# picoAvaR8.net
KiCad netlist of a schematic drawn in EAGLE
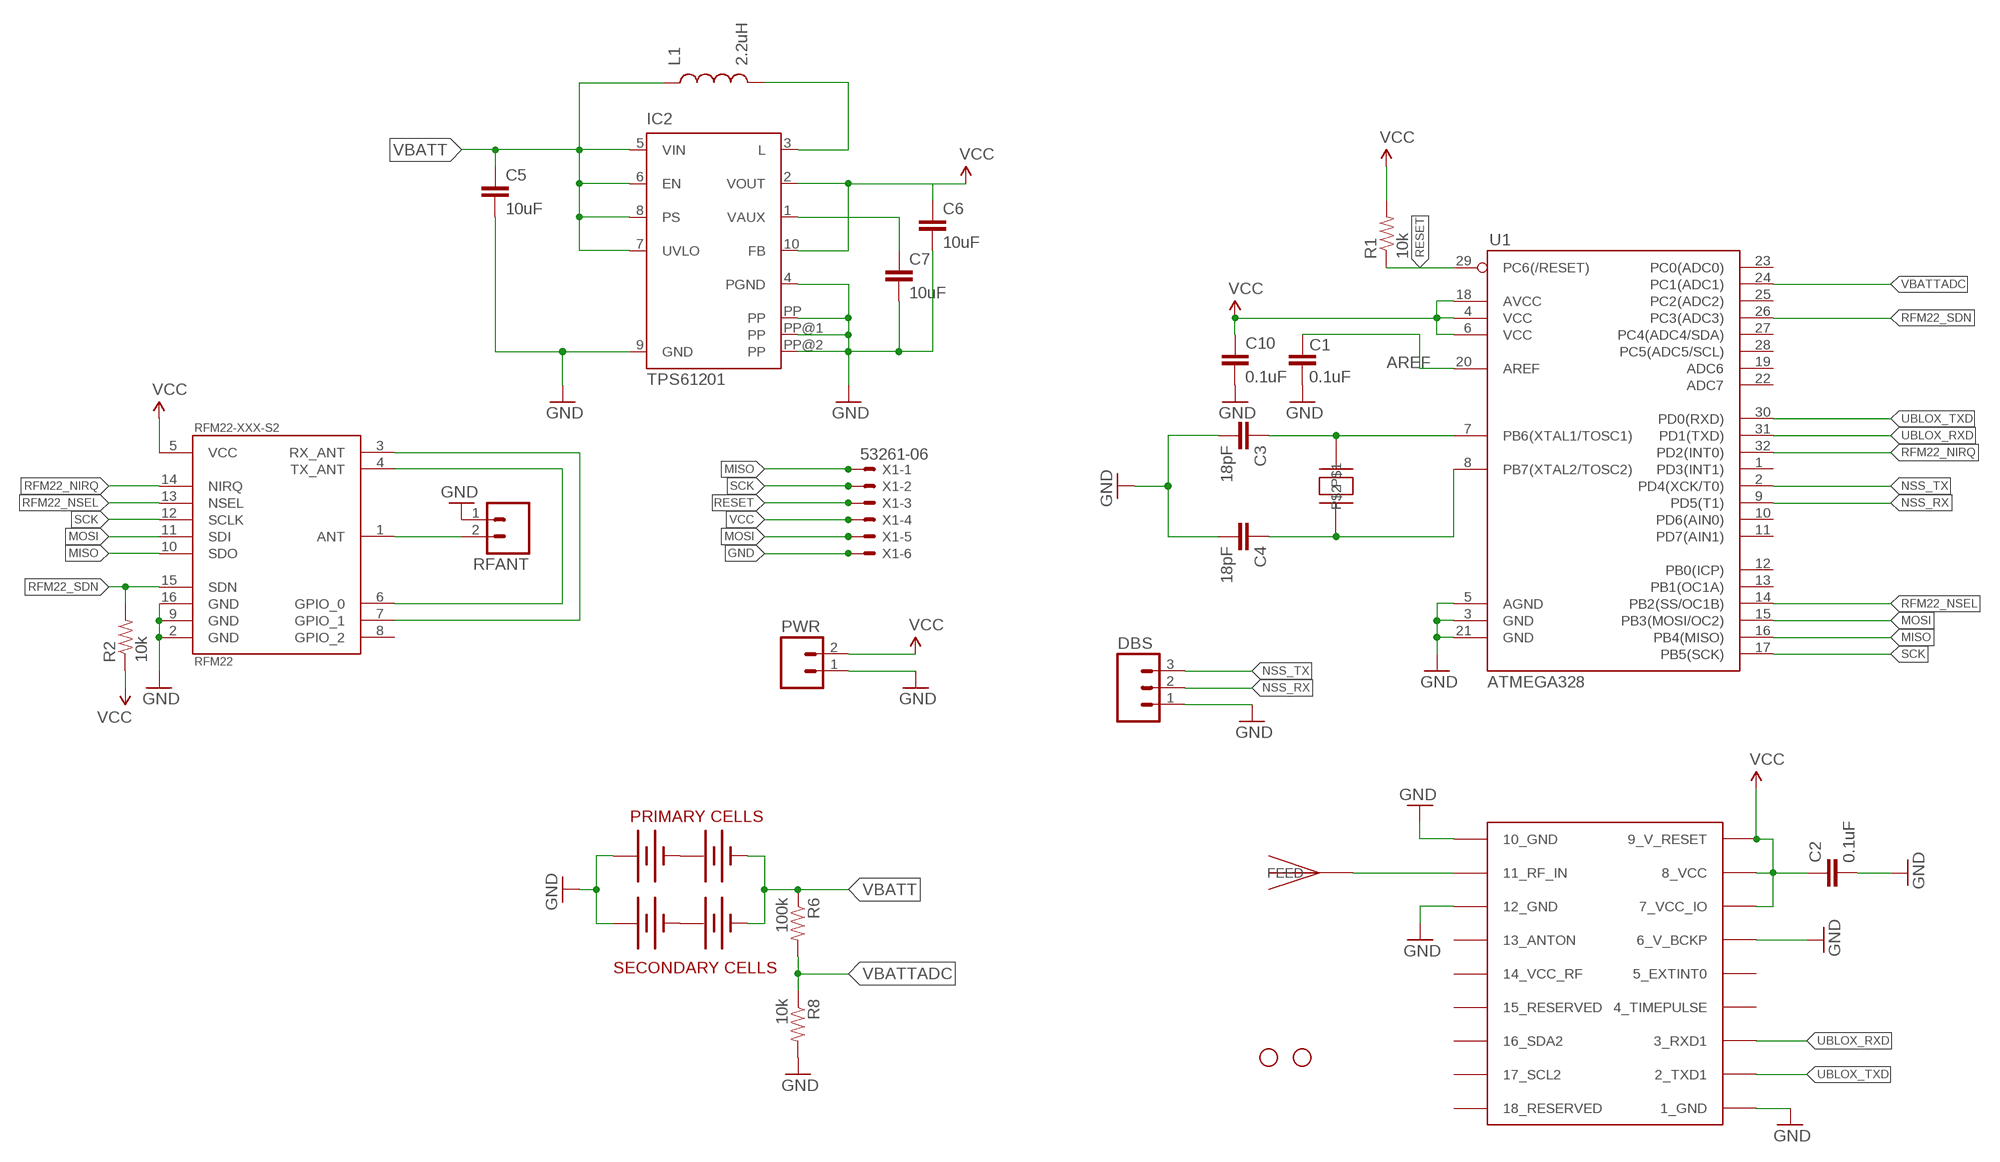
[diagram p0: schematic, sheet 1]

(export (version "E")
  (design (tool "Eeschema 10.0.6"))
  (components
    (comp (ref "C1")
      (value "0.1uF")
      (footprint "eagle-import:0402-CAP")
      (libsource (lib "eagle-import") (part "CAP0402-CAP"))
    )
    (comp (ref "C2")
      (value "0.1uF")
      (footprint "eagle-import:0402-CAP")
      (libsource (lib "eagle-import") (part "CAP0402-CAP"))
    )
    (comp (ref "C3")
      (value "18pF")
      (footprint "eagle-import:0402-CAP")
      (libsource (lib "eagle-import") (part "CAP0402-CAP"))
    )
    (comp (ref "C4")
      (value "18pF")
      (footprint "eagle-import:0402-CAP")
      (libsource (lib "eagle-import") (part "CAP0402-CAP"))
    )
    (comp (ref "C5")
      (value "10uF")
      (footprint "eagle-import:1206")
      (libsource (lib "eagle-import") (part "CAP1206"))
    )
    (comp (ref "C6")
      (value "10uF")
      (footprint "eagle-import:1206")
      (libsource (lib "eagle-import") (part "CAP1206"))
    )
    (comp (ref "C7")
      (value "10uF")
      (footprint "eagle-import:1206")
      (libsource (lib "eagle-import") (part "CAP1206"))
    )
    (comp (ref "C10")
      (value "0.1uF")
      (footprint "eagle-import:0402-CAP")
      (libsource (lib "eagle-import") (part "CAP0402-CAP"))
    )
    (comp (ref "DBS")
      (value "M03PTH")
      (footprint "eagle-import:1X03")
      (libsource (lib "eagle-import") (part "M03PTH"))
    )
    (comp (ref "IC2")
      (value "TPS61201")
      (footprint "eagle-import:S-PDSO-N10")
      (fields (field (name "MPN") "TPS61201DRCT"))
      (libsource (lib "eagle-import") (part "TPS61201"))
    )
    (comp (ref "JP1")
      (value "STAND-OFF")
      (footprint "eagle-import:STAND-OFF")
      (libsource (lib "eagle-import") (part "STAND-OFF"))
    )
    (comp (ref "JP2")
      (value "STAND-OFF")
      (footprint "eagle-import:STAND-OFF")
      (libsource (lib "eagle-import") (part "STAND-OFF"))
    )
    (comp (ref "L1")
      (value "2.2uH")
      (footprint "eagle-import:ELLVGG_INDUCTOR")
      (libsource (lib "eagle-import") (part "ELLVGG_INDUCTOR"))
    )
    (comp (ref "PC1")
      (value "PC1")
      (footprint "eagle-import:TEST")
      (libsource (lib "eagle-import") (part "TEST"))
    )
    (comp (ref "PC2")
      (value "TEST")
      (footprint "eagle-import:TEST")
      (libsource (lib "eagle-import") (part "TEST"))
    )
    (comp (ref "PWR")
      (value "M02PTH")
      (footprint "eagle-import:1X02")
      (libsource (lib "eagle-import") (part "M02PTH"))
    )
    (comp (ref "R1")
      (value "10k")
      (footprint "eagle-import:0402-RES")
      (libsource (lib "eagle-import") (part "RESISTOR0402-RES"))
    )
    (comp (ref "R2")
      (value "10k")
      (footprint "eagle-import:0402-RES")
      (libsource (lib "eagle-import") (part "RESISTOR0402-RES"))
    )
    (comp (ref "R6")
      (value "100k")
      (footprint "eagle-import:0402-RES")
      (libsource (lib "eagle-import") (part "RESISTOR0402-RES"))
    )
    (comp (ref "R8")
      (value "10k")
      (footprint "eagle-import:0402-RES")
      (libsource (lib "eagle-import") (part "RESISTOR0402-RES"))
    )
    (comp (ref "RFANT")
      (value "M02PTH")
      (footprint "eagle-import:1X02")
      (libsource (lib "eagle-import") (part "M02PTH"))
    )
    (comp (ref "RFM22-XXX-S2")
      (value "RFM22")
      (footprint "eagle-import:RFM22-XXX-S2")
      (libsource (lib "eagle-import") (part "RFM22"))
    )
    (comp (ref "SC1")
      (value "TEST")
      (footprint "eagle-import:TEST")
      (libsource (lib "eagle-import") (part "TEST"))
    )
    (comp (ref "SC2")
      (value "TEST")
      (footprint "eagle-import:TEST")
      (libsource (lib "eagle-import") (part "TEST"))
    )
    (comp (ref "U$1")
      (value "UBLOX_MAX-6")
      (footprint "eagle-import:UBLOX_MAX-6")
      (libsource (lib "eagle-import") (part "UBLOX_MAX-6"))
    )
    (comp (ref "U$2")
      (value "ABRACON_ABM3_CRYSTAL")
      (footprint "eagle-import:ABRACON_ABM3_CRYSTAL")
      (libsource (lib "eagle-import") (part "ABRACON_ABM3_CRYSTAL"))
    )
    (comp (ref "U$3")
      (value "JTI_ANTENNA-1575AT43A40")
      (footprint "eagle-import:JTI_ANTENNA-1575AT43A40")
      (libsource (lib "eagle-import") (part "JTI_ANTENNA-1575AT43A40"))
    )
    (comp (ref "U1")
      (value "ATMEGA328")
      (footprint "eagle-import:TQFP32-08")
      (libsource (lib "eagle-import") (part "ATMEGA168"))
    )
    (comp (ref "X1")
      (value "53261-06")
      (footprint "eagle-import:53261-06")
      (libsource (lib "eagle-import") (part "53?-06261"))
    )
  )
  (nets
    (net (code "1") (name "/AREF") (class "Default")
      (node (ref "C1") (pin "2") (pinfunction "2_2") (pintype "passive"))
      (node (ref "U1") (pin "20") (pinfunction "AREF_20") (pintype "bidirectional"))
    )
    (net (code "2") (name "GND") (class "Default")
      (node (ref "C1") (pin "1") (pinfunction "1_1") (pintype "passive"))
      (node (ref "C10") (pin "2") (pinfunction "2_2") (pintype "passive"))
      (node (ref "C2") (pin "2") (pinfunction "2_2") (pintype "passive"))
      (node (ref "C3") (pin "2") (pinfunction "2_2") (pintype "passive"))
      (node (ref "C4") (pin "2") (pinfunction "2_2") (pintype "passive"))
      (node (ref "C5") (pin "2") (pinfunction "2_2") (pintype "passive"))
      (node (ref "C6") (pin "2") (pinfunction "2_2") (pintype "passive"))
      (node (ref "C7") (pin "2") (pinfunction "2_2") (pintype "passive"))
      (node (ref "DBS") (pin "1") (pinfunction "1_1") (pintype "passive"))
      (node (ref "IC2") (pin "4") (pinfunction "PGND_4") (pintype "power_in"))
      (node (ref "IC2") (pin "9") (pinfunction "GND_9") (pintype "power_in"))
      (node (ref "IC2") (pin "PP") (pinfunction "PP_PP") (pintype "power_in"))
      (node (ref "IC2") (pin "PP@1") (pinfunction "PP_PP@1") (pintype "power_in"))
      (node (ref "IC2") (pin "PP@2") (pinfunction "PP_PP@2") (pintype "power_in"))
      (node (ref "PC1") (pin "VBATT") (pinfunction "+_VBATT") (pintype "power_in"))
      (node (ref "PC1") (pin "VBATT1") (pinfunction "+_VBATT1") (pintype "power_in"))
      (node (ref "PWR") (pin "1") (pinfunction "1_1") (pintype "passive"))
      (node (ref "R8") (pin "2") (pinfunction "2_2") (pintype "passive"))
      (node (ref "RFANT") (pin "1") (pinfunction "1_1") (pintype "passive"))
      (node (ref "RFM22-XXX-S2") (pin "16") (pinfunction "GND_16") (pintype "power_in"))
      (node (ref "RFM22-XXX-S2") (pin "2") (pinfunction "GND_2") (pintype "power_in"))
      (node (ref "RFM22-XXX-S2") (pin "9") (pinfunction "GND_9") (pintype "power_in"))
      (node (ref "SC1") (pin "VBATT") (pinfunction "+_VBATT") (pintype "power_in"))
      (node (ref "SC1") (pin "VBATT1") (pinfunction "+_VBATT1") (pintype "power_in"))
      (node (ref "U$1") (pin "10_GND") (pinfunction "10_GND_10_GND") (pintype "bidirectional"))
      (node (ref "U$1") (pin "12_GND") (pinfunction "12_GND_12_GND") (pintype "bidirectional"))
      (node (ref "U$1") (pin "1_GND") (pinfunction "1_GND_1_GND") (pintype "bidirectional"))
      (node (ref "U$1") (pin "6_V_BCKP") (pinfunction "6_V_BCKP_6_V_BCKP") (pintype "bidirectional"))
      (node (ref "U1") (pin "21") (pinfunction "GND_21") (pintype "bidirectional"))
      (node (ref "U1") (pin "3") (pinfunction "GND_3") (pintype "bidirectional"))
      (node (ref "U1") (pin "5") (pinfunction "AGND_5") (pintype "bidirectional"))
      (node (ref "X1") (pin "6") (pinfunction "S_6") (pintype "passive"))
    )
    (net (code "3") (name "MISO") (class "Default")
      (node (ref "RFM22-XXX-S2") (pin "10") (pinfunction "SDO_10") (pintype "output"))
      (node (ref "U1") (pin "16") (pinfunction "PB4(MISO)_16") (pintype "bidirectional"))
      (node (ref "X1") (pin "1") (pinfunction "S_1") (pintype "passive"))
    )
    (net (code "4") (name "MOSI") (class "Default")
      (node (ref "RFM22-XXX-S2") (pin "11") (pinfunction "SDI_11") (pintype "input"))
      (node (ref "U1") (pin "15") (pinfunction "PB3(MOSI/OC2)_15") (pintype "bidirectional"))
      (node (ref "X1") (pin "5") (pinfunction "S_5") (pintype "passive"))
    )
    (net (code "5") (name "NSS_RX") (class "Default")
      (node (ref "DBS") (pin "2") (pinfunction "2_2") (pintype "passive"))
      (node (ref "U1") (pin "9") (pinfunction "PD5(T1)_9") (pintype "bidirectional"))
    )
    (net (code "6") (name "NSS_TX") (class "Default")
      (node (ref "DBS") (pin "3") (pinfunction "3_3") (pintype "passive"))
      (node (ref "U1") (pin "2") (pinfunction "PD4(XCK/T0)_2") (pintype "bidirectional"))
    )
    (net (code "7") (name "Net-(IC2-L)") (class "Default")
      (node (ref "IC2") (pin "3") (pinfunction "L_3") (pintype "input"))
      (node (ref "L1") (pin "P$2") (pinfunction "2_P$2") (pintype "passive"))
    )
    (net (code "8") (name "Net-(IC2-VAUX)") (class "Default")
      (node (ref "C7") (pin "1") (pinfunction "1_1") (pintype "passive"))
      (node (ref "IC2") (pin "1") (pinfunction "VAUX_1") (pintype "bidirectional"))
    )
    (net (code "9") (name "Net-(PC1---PadGND)") (class "Default")
      (node (ref "PC1") (pin "GND") (pinfunction "-_GND") (pintype "power_in"))
      (node (ref "PC1") (pin "GND2") (pinfunction "-_GND2") (pintype "power_in"))
      (node (ref "PC2") (pin "VBATT") (pinfunction "+_VBATT") (pintype "power_in"))
      (node (ref "PC2") (pin "VBATT1") (pinfunction "+_VBATT1") (pintype "power_in"))
    )
    (net (code "10") (name "Net-(RFM22-XXX-S2-ANT)") (class "Default")
      (node (ref "RFANT") (pin "2") (pinfunction "2_2") (pintype "passive"))
      (node (ref "RFM22-XXX-S2") (pin "1") (pinfunction "ANT_1") (pintype "bidirectional"))
    )
    (net (code "11") (name "Net-(RFM22-XXX-S2-GPIO_0)") (class "Default")
      (node (ref "RFM22-XXX-S2") (pin "4") (pinfunction "TX_ANT_4") (pintype "input"))
      (node (ref "RFM22-XXX-S2") (pin "6") (pinfunction "GPIO_0_6") (pintype "bidirectional"))
    )
    (net (code "12") (name "Net-(RFM22-XXX-S2-GPIO_1)") (class "Default")
      (node (ref "RFM22-XXX-S2") (pin "3") (pinfunction "RX_ANT_3") (pintype "input"))
      (node (ref "RFM22-XXX-S2") (pin "7") (pinfunction "GPIO_1_7") (pintype "bidirectional"))
    )
    (net (code "13") (name "Net-(SC1---PadGND)") (class "Default")
      (node (ref "SC1") (pin "GND") (pinfunction "-_GND") (pintype "power_in"))
      (node (ref "SC1") (pin "GND2") (pinfunction "-_GND2") (pintype "power_in"))
      (node (ref "SC2") (pin "VBATT") (pinfunction "+_VBATT") (pintype "power_in"))
      (node (ref "SC2") (pin "VBATT1") (pinfunction "+_VBATT1") (pintype "power_in"))
    )
    (net (code "14") (name "Net-(U$1-Pad11_RF_IN)") (class "Default")
      (node (ref "U$1") (pin "11_RF_IN") (pinfunction "11_RF_IN_11_RF_IN") (pintype "bidirectional"))
      (node (ref "U$3") (pin "FEED") (pinfunction "FEED_FEED") (pintype "bidirectional"))
    )
    (net (code "15") (name "Net-(U1-PB6(XTAL1{slash}TOSC1))") (class "Default")
      (node (ref "C3") (pin "1") (pinfunction "1_1") (pintype "passive"))
      (node (ref "U$2") (pin "P$2") (pinfunction "P$2_P$2") (pintype "bidirectional"))
      (node (ref "U1") (pin "7") (pinfunction "PB6(XTAL1/TOSC1)_7") (pintype "bidirectional"))
    )
    (net (code "16") (name "Net-(U1-PB7(XTAL2{slash}TOSC2))") (class "Default")
      (node (ref "C4") (pin "1") (pinfunction "1_1") (pintype "passive"))
      (node (ref "U$2") (pin "P$1") (pinfunction "P$1_P$1") (pintype "bidirectional"))
      (node (ref "U1") (pin "8") (pinfunction "PB7(XTAL2/TOSC2)_8") (pintype "bidirectional"))
    )
    (net (code "17") (name "RESET") (class "Default")
      (node (ref "R1") (pin "1") (pinfunction "1_1") (pintype "passive"))
      (node (ref "U1") (pin "29") (pinfunction "PC6(/RESET)_29") (pintype "bidirectional"))
      (node (ref "X1") (pin "3") (pinfunction "S_3") (pintype "passive"))
    )
    (net (code "18") (name "RFM22_NIRQ") (class "Default")
      (node (ref "RFM22-XXX-S2") (pin "14") (pinfunction "NIRQ_14") (pintype "output"))
      (node (ref "U1") (pin "32") (pinfunction "PD2(INT0)_32") (pintype "bidirectional"))
    )
    (net (code "19") (name "RFM22_NSEL") (class "Default")
      (node (ref "RFM22-XXX-S2") (pin "13") (pinfunction "NSEL_13") (pintype "input"))
      (node (ref "U1") (pin "14") (pinfunction "PB2(SS/OC1B)_14") (pintype "bidirectional"))
    )
    (net (code "20") (name "RFM22_SDN") (class "Default")
      (node (ref "R2") (pin "2") (pinfunction "2_2") (pintype "passive"))
      (node (ref "RFM22-XXX-S2") (pin "15") (pinfunction "SDN_15") (pintype "input"))
      (node (ref "U1") (pin "26") (pinfunction "PC3(ADC3)_26") (pintype "bidirectional"))
    )
    (net (code "21") (name "SCK") (class "Default")
      (node (ref "RFM22-XXX-S2") (pin "12") (pinfunction "SCLK_12") (pintype "input"))
      (node (ref "U1") (pin "17") (pinfunction "PB5(SCK)_17") (pintype "bidirectional"))
      (node (ref "X1") (pin "2") (pinfunction "S_2") (pintype "passive"))
    )
    (net (code "22") (name "UBLOX_RXD") (class "Default")
      (node (ref "U$1") (pin "3_RXD1") (pinfunction "3_RXD1_3_RXD1") (pintype "bidirectional"))
      (node (ref "U1") (pin "31") (pinfunction "PD1(TXD)_31") (pintype "bidirectional"))
    )
    (net (code "23") (name "UBLOX_TXD") (class "Default")
      (node (ref "U$1") (pin "2_TXD1") (pinfunction "2_TXD1_2_TXD1") (pintype "bidirectional"))
      (node (ref "U1") (pin "30") (pinfunction "PD0(RXD)_30") (pintype "bidirectional"))
    )
    (net (code "24") (name "VBATT") (class "Default")
      (node (ref "C5") (pin "1") (pinfunction "1_1") (pintype "passive"))
      (node (ref "IC2") (pin "5") (pinfunction "VIN_5") (pintype "input"))
      (node (ref "IC2") (pin "6") (pinfunction "EN_6") (pintype "input"))
      (node (ref "IC2") (pin "7") (pinfunction "UVLO_7") (pintype "input"))
      (node (ref "IC2") (pin "8") (pinfunction "PS_8") (pintype "input"))
      (node (ref "L1") (pin "P$1") (pinfunction "1_P$1") (pintype "passive"))
      (node (ref "PC2") (pin "GND") (pinfunction "-_GND") (pintype "power_in"))
      (node (ref "PC2") (pin "GND2") (pinfunction "-_GND2") (pintype "power_in"))
      (node (ref "R6") (pin "1") (pinfunction "1_1") (pintype "passive"))
      (node (ref "SC2") (pin "GND") (pinfunction "-_GND") (pintype "power_in"))
      (node (ref "SC2") (pin "GND2") (pinfunction "-_GND2") (pintype "power_in"))
    )
    (net (code "25") (name "VBATTADC") (class "Default")
      (node (ref "R6") (pin "2") (pinfunction "2_2") (pintype "passive"))
      (node (ref "R8") (pin "1") (pinfunction "1_1") (pintype "passive"))
      (node (ref "U1") (pin "24") (pinfunction "PC1(ADC1)_24") (pintype "bidirectional"))
    )
    (net (code "26") (name "VCC") (class "Default")
      (node (ref "C10") (pin "1") (pinfunction "1_1") (pintype "passive"))
      (node (ref "C2") (pin "1") (pinfunction "1_1") (pintype "passive"))
      (node (ref "C6") (pin "1") (pinfunction "1_1") (pintype "passive"))
      (node (ref "IC2") (pin "10") (pinfunction "FB_10") (pintype "input"))
      (node (ref "IC2") (pin "2") (pinfunction "VOUT_2") (pintype "passive"))
      (node (ref "PWR") (pin "2") (pinfunction "2_2") (pintype "passive"))
      (node (ref "R1") (pin "2") (pinfunction "2_2") (pintype "passive"))
      (node (ref "R2") (pin "1") (pinfunction "1_1") (pintype "passive"))
      (node (ref "RFM22-XXX-S2") (pin "5") (pinfunction "VCC_5") (pintype "bidirectional"))
      (node (ref "U$1") (pin "7_VCC_IO") (pinfunction "7_VCC_IO_7_VCC_IO") (pintype "bidirectional"))
      (node (ref "U$1") (pin "8_VCC") (pinfunction "8_VCC_8_VCC") (pintype "bidirectional"))
      (node (ref "U$1") (pin "9_V_RESET") (pinfunction "9_V_RESET_9_V_RESET") (pintype "bidirectional"))
      (node (ref "U1") (pin "18") (pinfunction "AVCC_18") (pintype "bidirectional"))
      (node (ref "U1") (pin "4") (pinfunction "VCC_4") (pintype "bidirectional"))
      (node (ref "U1") (pin "6") (pinfunction "VCC_6") (pintype "bidirectional"))
      (node (ref "X1") (pin "4") (pinfunction "S_4") (pintype "passive"))
    )
    (net (code "27") (name "unconnected-(RFM22-XXX-S2-GPIO_2-Pad8)") (class "Default")
      (node (ref "RFM22-XXX-S2") (pin "8") (pinfunction "GPIO_2_8") (pintype "bidirectional"))
    )
    (net (code "28") (name "unconnected-(U$1-Pad4_TIMEPULSE)") (class "Default")
      (node (ref "U$1") (pin "4_TIMEPULSE") (pinfunction "4_TIMEPULSE_4_TIMEPULSE") (pintype "bidirectional"))
    )
    (net (code "29") (name "unconnected-(U$1-Pad5_EXTINT0)") (class "Default")
      (node (ref "U$1") (pin "5_EXTINT0") (pinfunction "5_EXTINT0_5_EXTINT0") (pintype "bidirectional"))
    )
    (net (code "30") (name "unconnected-(U$1-Pad13_ANTON)") (class "Default")
      (node (ref "U$1") (pin "13_ANTON") (pinfunction "13_ANTON_13_ANTON") (pintype "bidirectional"))
    )
    (net (code "31") (name "unconnected-(U$1-Pad14_VCC_RF)") (class "Default")
      (node (ref "U$1") (pin "14_VCC_RF") (pinfunction "14_VCC_RF_14_VCC_RF") (pintype "bidirectional"))
    )
    (net (code "32") (name "unconnected-(U$1-Pad15_RESERVED)") (class "Default")
      (node (ref "U$1") (pin "15_RESERVED") (pinfunction "15_RESERVED_15_RESERVED") (pintype "bidirectional"))
    )
    (net (code "33") (name "unconnected-(U$1-Pad16_SDA2)") (class "Default")
      (node (ref "U$1") (pin "16_SDA2") (pinfunction "16_SDA2_16_SDA2") (pintype "bidirectional"))
    )
    (net (code "34") (name "unconnected-(U$1-Pad17_SCL2)") (class "Default")
      (node (ref "U$1") (pin "17_SCL2") (pinfunction "17_SCL2_17_SCL2") (pintype "bidirectional"))
    )
    (net (code "35") (name "unconnected-(U$1-Pad18_RESERVED)") (class "Default")
      (node (ref "U$1") (pin "18_RESERVED") (pinfunction "18_RESERVED_18_RESERVED") (pintype "bidirectional"))
    )
    (net (code "36") (name "unconnected-(U1-ADC6-Pad19)") (class "Default")
      (node (ref "U1") (pin "19") (pinfunction "ADC6_19") (pintype "bidirectional"))
    )
    (net (code "37") (name "unconnected-(U1-ADC7-Pad22)") (class "Default")
      (node (ref "U1") (pin "22") (pinfunction "ADC7_22") (pintype "bidirectional"))
    )
    (net (code "38") (name "unconnected-(U1-PB0(ICP)-Pad12)") (class "Default")
      (node (ref "U1") (pin "12") (pinfunction "PB0(ICP)_12") (pintype "bidirectional"))
    )
    (net (code "39") (name "unconnected-(U1-PB1(OC1A)-Pad13)") (class "Default")
      (node (ref "U1") (pin "13") (pinfunction "PB1(OC1A)_13") (pintype "bidirectional"))
    )
    (net (code "40") (name "unconnected-(U1-PC0(ADC0)-Pad23)") (class "Default")
      (node (ref "U1") (pin "23") (pinfunction "PC0(ADC0)_23") (pintype "bidirectional"))
    )
    (net (code "41") (name "unconnected-(U1-PC2(ADC2)-Pad25)") (class "Default")
      (node (ref "U1") (pin "25") (pinfunction "PC2(ADC2)_25") (pintype "bidirectional"))
    )
    (net (code "42") (name "unconnected-(U1-PC4(ADC4{slash}SDA)-Pad27)") (class "Default")
      (node (ref "U1") (pin "27") (pinfunction "PC4(ADC4/SDA)_27") (pintype "bidirectional"))
    )
    (net (code "43") (name "unconnected-(U1-PC5(ADC5{slash}SCL)-Pad28)") (class "Default")
      (node (ref "U1") (pin "28") (pinfunction "PC5(ADC5/SCL)_28") (pintype "bidirectional"))
    )
    (net (code "44") (name "unconnected-(U1-PD3(INT1)-Pad1)") (class "Default")
      (node (ref "U1") (pin "1") (pinfunction "PD3(INT1)_1") (pintype "bidirectional"))
    )
    (net (code "45") (name "unconnected-(U1-PD6(AIN0)-Pad10)") (class "Default")
      (node (ref "U1") (pin "10") (pinfunction "PD6(AIN0)_10") (pintype "bidirectional"))
    )
    (net (code "46") (name "unconnected-(U1-PD7(AIN1)-Pad11)") (class "Default")
      (node (ref "U1") (pin "11") (pinfunction "PD7(AIN1)_11") (pintype "bidirectional"))
    )
  )
)
